# SparkFun_GPS_RTK_Surveyor.net
KiCad netlist of a schematic drawn in EAGLE
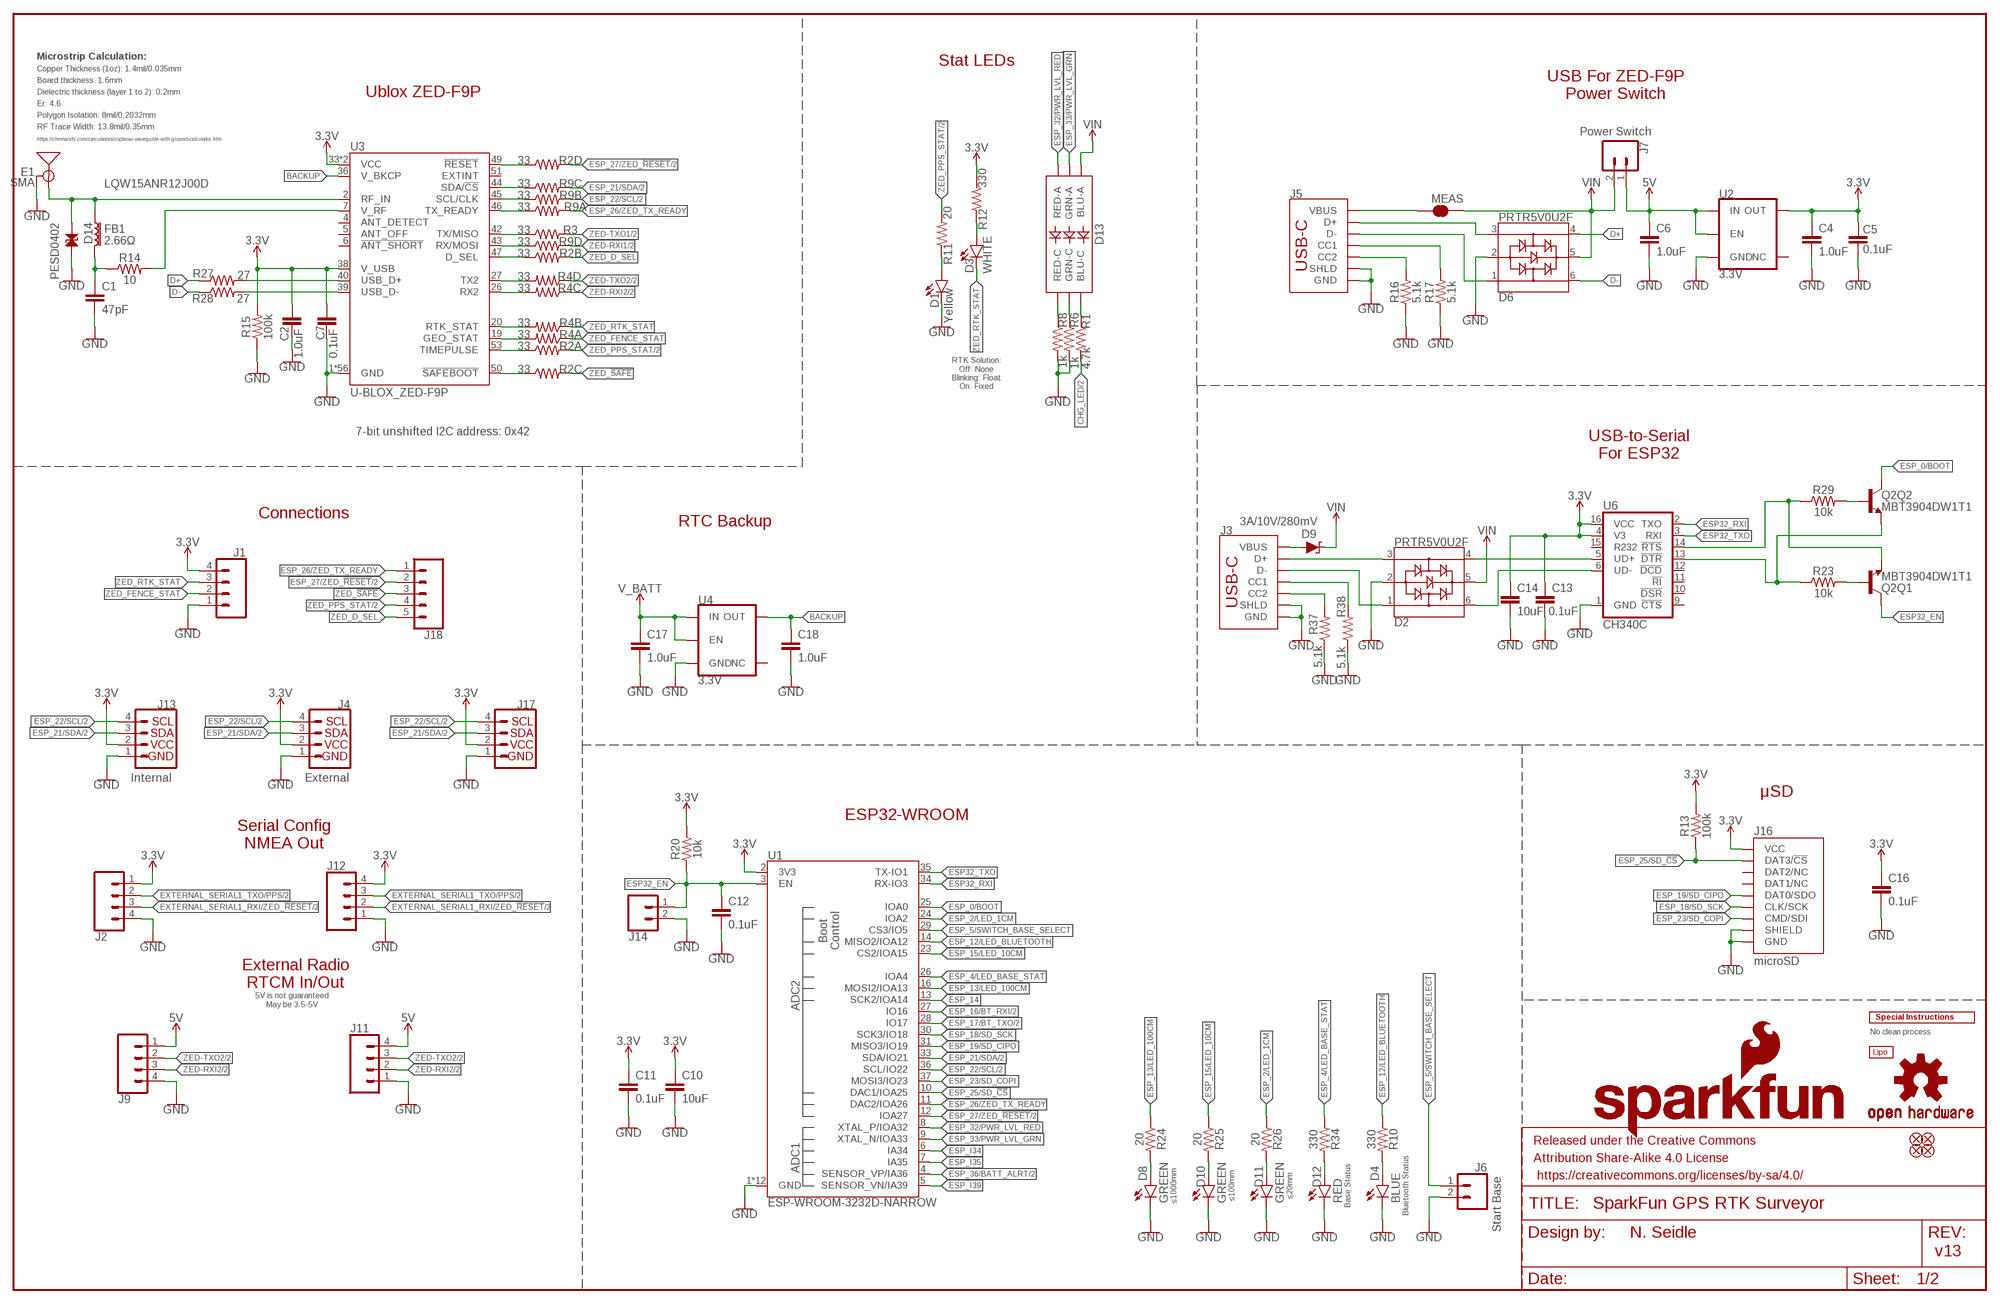
[diagram p0: schematic, sheet 1]
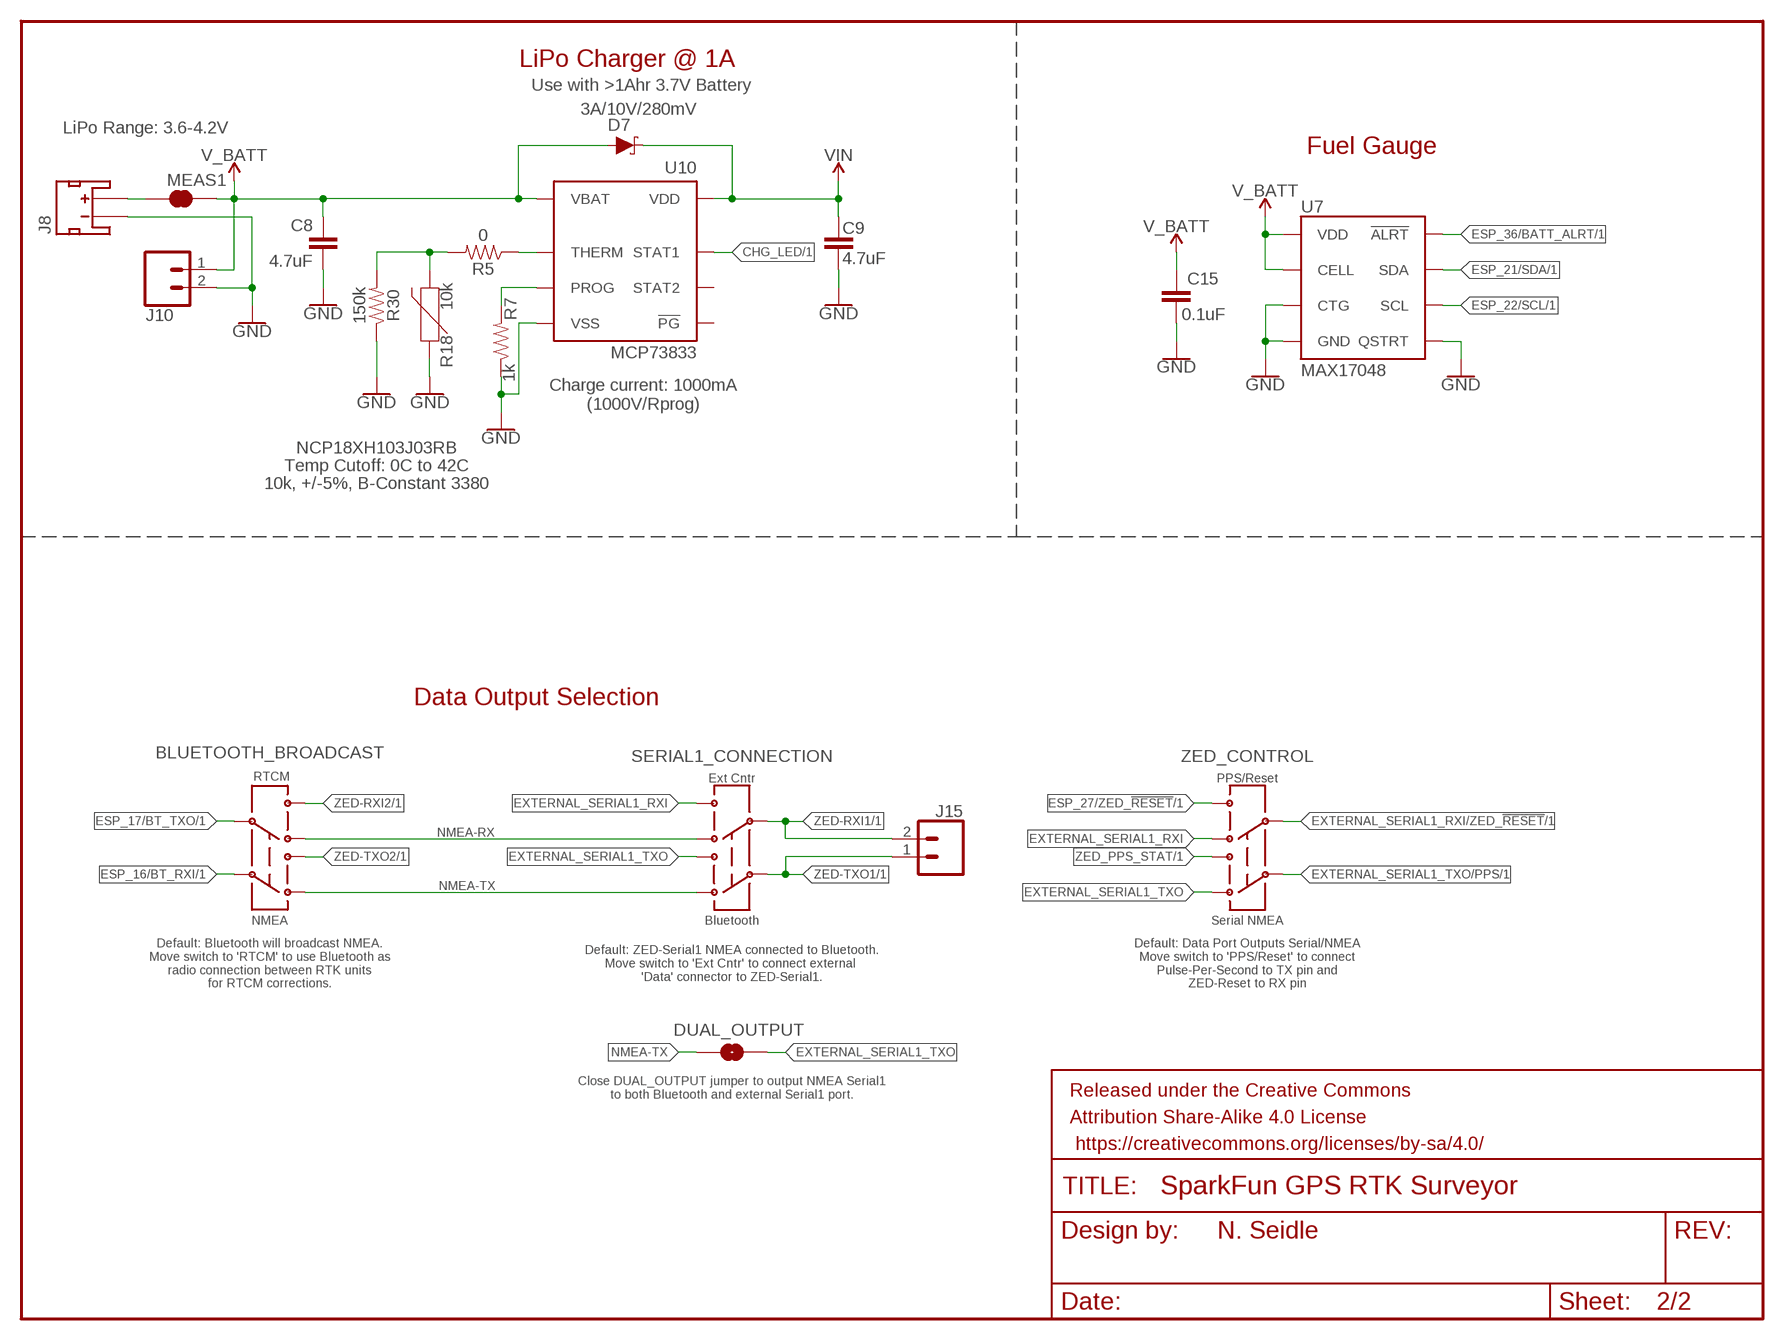
[diagram p1: schematic, sheet 2]

(export (version "E")
  (design (tool "Eeschema 10.0.6"))
  (components
    (comp (ref "BT1")
      (value "LIPO-OUTLINE1000")
      (footprint "eagle-import:LIPO-1000")
      (libsource (lib "eagle-import") (part "LIPO-OUTLINE1000"))
    )
    (comp (ref "C1")
      (value "47pF")
      (footprint "eagle-import:0402")
      (libsource (lib "eagle-import") (part "47PF-0402-25V-5%-X7R"))
    )
    (comp (ref "C2")
      (value "1.0uF")
      (footprint "eagle-import:0603")
      (libsource (lib "eagle-import") (part "1.0UF-0603-16V-10%-X7R"))
    )
    (comp (ref "C4")
      (value "1.0uF")
      (footprint "eagle-import:0603")
      (libsource (lib "eagle-import") (part "1.0UF-0603-16V-10%-X7R"))
    )
    (comp (ref "C5")
      (value "0.1uF")
      (footprint "eagle-import:0603")
      (libsource (lib "eagle-import") (part "0.1UF-0603-25V-5%"))
    )
    (comp (ref "C6")
      (value "1.0uF")
      (footprint "eagle-import:0603")
      (libsource (lib "eagle-import") (part "1.0UF-0603-16V-10%-X7R"))
    )
    (comp (ref "C7")
      (value "0.1uF")
      (footprint "eagle-import:0603")
      (libsource (lib "eagle-import") (part "0.1UF-0603-25V-5%"))
    )
    (comp (ref "C10")
      (value "10uF")
      (footprint "eagle-import:0603")
      (libsource (lib "eagle-import") (part "10UF-0603-6.3V-20%"))
    )
    (comp (ref "C11")
      (value "0.1uF")
      (footprint "eagle-import:0603")
      (libsource (lib "eagle-import") (part "0.1UF-0603-25V-(+80/-20%)"))
    )
    (comp (ref "C12")
      (value "0.1uF")
      (footprint "eagle-import:0603")
      (libsource (lib "eagle-import") (part "0.1UF-0603-25V-(+80/-20%)"))
    )
    (comp (ref "C13")
      (value "0.1uF")
      (footprint "eagle-import:0603")
      (libsource (lib "eagle-import") (part "0.1UF-0603-25V-(+80/-20%)"))
    )
    (comp (ref "C14")
      (value "10uF")
      (footprint "eagle-import:0603")
      (libsource (lib "eagle-import") (part "10UF-0603-6.3V-20%"))
    )
    (comp (ref "C16")
      (value "0.1uF")
      (footprint "eagle-import:0603")
      (libsource (lib "eagle-import") (part "0.1UF-0603-25V-(+80/-20%)"))
    )
    (comp (ref "C17")
      (value "1.0uF")
      (footprint "eagle-import:0603")
      (libsource (lib "eagle-import") (part "1.0UF-0603-16V-10%-X7R"))
    )
    (comp (ref "C18")
      (value "1.0uF")
      (footprint "eagle-import:0603")
      (libsource (lib "eagle-import") (part "1.0UF-0603-16V-10%-X7R"))
    )
    (comp (ref "D1")
      (value "Yellow")
      (footprint "eagle-import:LED-0603")
      (libsource (lib "eagle-import") (part "LED-YELLOW0603"))
    )
    (comp (ref "D2")
      (value "PRTR5V0U2F")
      (footprint "eagle-import:SOT886")
      (libsource (lib "eagle-import") (part "PRTR5V0U2F"))
    )
    (comp (ref "D3")
      (value "WHITE")
      (footprint "eagle-import:LED-0603")
      (libsource (lib "eagle-import") (part "LED-WHITE0603"))
    )
    (comp (ref "D4")
      (value "BLUE")
      (footprint "eagle-import:LED-0603")
      (libsource (lib "eagle-import") (part "LED-BLUE0603"))
    )
    (comp (ref "D6")
      (value "PRTR5V0U2F")
      (footprint "eagle-import:SOT886")
      (libsource (lib "eagle-import") (part "PRTR5V0U2F"))
    )
    (comp (ref "D8")
      (value "GREEN")
      (footprint "eagle-import:LED-0603")
      (libsource (lib "eagle-import") (part "LED-GREEN0603"))
    )
    (comp (ref "D9")
      (value "3A/10V/280mV")
      (footprint "eagle-import:SOD-323")
      (libsource (lib "eagle-import") (part "DIODE-SCHOTTKY-BAT60A"))
    )
    (comp (ref "D10")
      (value "GREEN")
      (footprint "eagle-import:LED-0603")
      (libsource (lib "eagle-import") (part "LED-GREEN0603"))
    )
    (comp (ref "D11")
      (value "GREEN")
      (footprint "eagle-import:LED-0603")
      (libsource (lib "eagle-import") (part "LED-GREEN0603"))
    )
    (comp (ref "D12")
      (value "RED")
      (footprint "eagle-import:LED-0603")
      (libsource (lib "eagle-import") (part "LED-RED0603"))
    )
    (comp (ref "D13")
      (value "LED-RGBBRG")
      (footprint "eagle-import:LED-TRICOLOR-5050")
      (libsource (lib "eagle-import") (part "LED-RGBBRG"))
    )
    (comp (ref "D14")
      (value "PESD0402")
      (footprint "eagle-import:0402")
      (fields
        (field (name "DIGIKEY_PART") "PESD0402-140CT-ND")
        (field (name "MOUSE_PART") "650-PESD0402-140")
      )
      (libsource (lib "eagle-import") (part "PESD0402"))
    )
    (comp (ref "E1")
      (value "SMA")
      (footprint "eagle-import:SMA-EDGE")
      (libsource (lib "eagle-import") (part "ANTENNA-SMA-GROUNDEDEDGE_SMA"))
    )
    (comp (ref "FB1")
      (value "2.66Ω")
      (footprint "eagle-import:0402-TIGHT")
      (libsource (lib "eagle-import") (part "FERRITE_BEAD-0402-2.66Ω-1GHZ"))
    )
    (comp (ref "FRAME2")
      (value "FRAME-LEDGER")
      (footprint "eagle-import:CREATIVE_COMMONS")
      (libsource (lib "eagle-import") (part "FRAME-LEDGER"))
    )
    (comp (ref "J1")
      (value "CONN_041X04_NO_SILK_NO_POP")
      (footprint "eagle-import:1X04_NO_SILK")
      (libsource (lib "eagle-import") (part "CONN_041X04_NO_SILK_NO_POP"))
    )
    (comp (ref "J2")
      (value "CONN_04JST-SMD-LOCKING")
      (footprint "eagle-import:JST-4-SMD-1.25MM-LOCKING")
      (libsource (lib "eagle-import") (part "CONN_04JST-SMD-LOCKING"))
    )
    (comp (ref "J3")
      (value "USB Female Type C Connector")
      (footprint "eagle-import:USB-C-16P_4LAYER-PADS")
      (libsource (lib "eagle-import") (part "USB_C_4-LAYER_PADS"))
    )
    (comp (ref "J4")
      (value "External")
      (footprint "eagle-import:JST04_1MM_RA")
      (libsource (lib "eagle-import") (part "I2C_STANDARDQWIIC"))
    )
    (comp (ref "J5")
      (value "USB Female Type C Connector")
      (footprint "eagle-import:USB-C-16P_4LAYER-PADS")
      (libsource (lib "eagle-import") (part "USB_C_4-LAYER_PADS"))
    )
    (comp (ref "J6")
      (value "Start Base")
      (footprint "eagle-import:JST-2-SMD")
      (libsource (lib "eagle-import") (part "CONN_02-JST-2MM-SMT"))
    )
    (comp (ref "J7")
      (value "Power Switch")
      (footprint "eagle-import:JST-2-SMD")
      (libsource (lib "eagle-import") (part "CONN_02-JST-2MM-SMT"))
    )
    (comp (ref "J9")
      (value "CONN_04JST-SMD-LOCKING")
      (footprint "eagle-import:JST-4-SMD-1.25MM-LOCKING")
      (libsource (lib "eagle-import") (part "CONN_04JST-SMD-LOCKING"))
    )
    (comp (ref "J11")
      (value "CONN_041X04_NO_SILK_NO_POP")
      (footprint "eagle-import:1X04_NO_SILK")
      (libsource (lib "eagle-import") (part "CONN_041X04_NO_SILK_NO_POP"))
    )
    (comp (ref "J12")
      (value "CONN_041X04_NO_SILK_NO_POP")
      (footprint "eagle-import:1X04_NO_SILK")
      (libsource (lib "eagle-import") (part "CONN_041X04_NO_SILK_NO_POP"))
    )
    (comp (ref "J13")
      (value "Internal")
      (footprint "eagle-import:JST04_1MM_RA")
      (libsource (lib "eagle-import") (part "I2C_STANDARDQWIIC"))
    )
    (comp (ref "J14")
      (value "CONN_021X02_NO_SILK")
      (footprint "eagle-import:1X02_NO_SILK")
      (libsource (lib "eagle-import") (part "CONN_021X02_NO_SILK"))
    )
    (comp (ref "J16")
      (value "microSD")
      (footprint "eagle-import:MICRO-SD-SOCKET")
      (libsource (lib "eagle-import") (part "MICRO-SD-SDIOPUSH-PUSH"))
    )
    (comp (ref "J17")
      (value "Qwiic Right Angle")
      (footprint "eagle-import:1X04_NO_SILK")
      (libsource (lib "eagle-import") (part "I2C_STANDARD_NO_SILK"))
    )
    (comp (ref "J18")
      (value "CONN_05NO_SILK")
      (footprint "eagle-import:1X05_NO_SILK")
      (libsource (lib "eagle-import") (part "CONN_05NO_SILK"))
    )
    (comp (ref "JP21")
      (value "FIDUCIALUFIDUCIAL")
      (footprint "eagle-import:FIDUCIAL-MICRO")
      (libsource (lib "eagle-import") (part "FIDUCIALUFIDUCIAL"))
    )
    (comp (ref "JP61")
      (value "FIDUCIALUFIDUCIAL")
      (footprint "eagle-import:FIDUCIAL-MICRO")
      (libsource (lib "eagle-import") (part "FIDUCIALUFIDUCIAL"))
    )
    (comp (ref "JP71")
      (value "FIDUCIALUFIDUCIAL")
      (footprint "eagle-import:FIDUCIAL-MICRO")
      (libsource (lib "eagle-import") (part "FIDUCIALUFIDUCIAL"))
    )
    (comp (ref "JP81")
      (value "FIDUCIALUFIDUCIAL")
      (footprint "eagle-import:FIDUCIAL-MICRO")
      (libsource (lib "eagle-import") (part "FIDUCIALUFIDUCIAL"))
    )
    (comp (ref "LOGO1")
      (value "OSHW-LOGOMINI")
      (footprint "eagle-import:OSHW-LOGO-MINI")
      (libsource (lib "eagle-import") (part "OSHW-LOGOMINI"))
    )
    (comp (ref "LOGO2")
      (value "SFE_LOGO_NAME_FLAME.1_INCH")
      (footprint "eagle-import:SFE_LOGO_NAME_FLAME_.1")
      (libsource (lib "eagle-import") (part "SFE_LOGO_NAME_FLAME.1_INCH"))
    )
    (comp (ref "MEAS")
      (value "JUMPER-COMBO_2_NC_TRACE")
      (footprint "eagle-import:COMBO-JUMPER_2_NC_TRACE")
      (libsource (lib "eagle-import") (part "JUMPER-COMBO_2_NC_TRACE"))
    )
    (comp (ref "Q2")
      (value "MBT3904DW1T1")
      (footprint "eagle-import:SC70-6")
      (libsource (lib "eagle-import") (part "TRANS_NPN_DUAL-MBT3904DW1T1"))
    )
    (comp (ref "R1")
      (value "4.7k")
      (footprint "eagle-import:0603")
      (libsource (lib "eagle-import") (part "4.7KOHM-0603-1/10W-1%"))
    )
    (comp (ref "R2")
      (value "33")
      (footprint "eagle-import:1206_RA")
      (libsource (lib "eagle-import") (part "33OHM_RA-1206-1/16W-5%"))
    )
    (comp (ref "R3")
      (value "33")
      (footprint "eagle-import:0603")
      (libsource (lib "eagle-import") (part "33OHM-0603-1/10W-1%"))
    )
    (comp (ref "R4")
      (value "33")
      (footprint "eagle-import:1206_RA")
      (libsource (lib "eagle-import") (part "33OHM_RA-1206-1/16W-5%"))
    )
    (comp (ref "R6")
      (value "1k")
      (footprint "eagle-import:0603")
      (libsource (lib "eagle-import") (part "1KOHM-0603-1/10W-1%"))
    )
    (comp (ref "R8")
      (value "1k")
      (footprint "eagle-import:0603")
      (libsource (lib "eagle-import") (part "1KOHM-0603-1/10W-1%"))
    )
    (comp (ref "R9")
      (value "33")
      (footprint "eagle-import:1206_RA")
      (libsource (lib "eagle-import") (part "33OHM_RA-1206-1/16W-5%"))
    )
    (comp (ref "R10")
      (value "330")
      (footprint "eagle-import:0603")
      (libsource (lib "eagle-import") (part "330OHM-0603-1/10W-1%"))
    )
    (comp (ref "R11")
      (value "20")
      (footprint "eagle-import:0603")
      (libsource (lib "eagle-import") (part "20OHM-0603-1/10W-1%"))
    )
    (comp (ref "R12")
      (value "330")
      (footprint "eagle-import:0603")
      (libsource (lib "eagle-import") (part "330OHM-0603-1/10W-1%"))
    )
    (comp (ref "R13")
      (value "100k")
      (footprint "eagle-import:0603")
      (libsource (lib "eagle-import") (part "100KOHM-0603-1/10W-1%"))
    )
    (comp (ref "R14")
      (value "10")
      (footprint "eagle-import:0603")
      (libsource (lib "eagle-import") (part "10OHM-0603-1/10W-1%"))
    )
    (comp (ref "R15")
      (value "100k")
      (footprint "eagle-import:0603")
      (libsource (lib "eagle-import") (part "100KOHM-0603-1/10W-1%"))
    )
    (comp (ref "R16")
      (value "5.1k")
      (footprint "eagle-import:0603")
      (libsource (lib "eagle-import") (part "5.1KOHM5.1KOHM-0603-1/10W-1%"))
    )
    (comp (ref "R17")
      (value "5.1k")
      (footprint "eagle-import:0603")
      (libsource (lib "eagle-import") (part "5.1KOHM5.1KOHM-0603-1/10W-1%"))
    )
    (comp (ref "R20")
      (value "10k")
      (footprint "eagle-import:0603")
      (libsource (lib "eagle-import") (part "10KOHM-0603-1/10W-1%"))
    )
    (comp (ref "R23")
      (value "10k")
      (footprint "eagle-import:0603")
      (libsource (lib "eagle-import") (part "10KOHM-0603-1/10W-1%"))
    )
    (comp (ref "R24")
      (value "20")
      (footprint "eagle-import:0603")
      (libsource (lib "eagle-import") (part "20OHM-0603-1/10W-1%"))
    )
    (comp (ref "R25")
      (value "20")
      (footprint "eagle-import:0603")
      (libsource (lib "eagle-import") (part "20OHM-0603-1/10W-1%"))
    )
    (comp (ref "R26")
      (value "20")
      (footprint "eagle-import:0603")
      (libsource (lib "eagle-import") (part "20OHM-0603-1/10W-1%"))
    )
    (comp (ref "R27")
      (value "27")
      (footprint "eagle-import:0603")
      (libsource (lib "eagle-import") (part "27OHM-0603-1/10W-1%"))
    )
    (comp (ref "R28")
      (value "27")
      (footprint "eagle-import:0603")
      (libsource (lib "eagle-import") (part "27OHM-0603-1/10W-1%"))
    )
    (comp (ref "R29")
      (value "10k")
      (footprint "eagle-import:0603")
      (libsource (lib "eagle-import") (part "10KOHM-0603-1/10W-1%"))
    )
    (comp (ref "R34")
      (value "330")
      (footprint "eagle-import:0603")
      (libsource (lib "eagle-import") (part "330OHM-0603-1/10W-1%"))
    )
    (comp (ref "R37")
      (value "5.1k")
      (footprint "eagle-import:0603")
      (libsource (lib "eagle-import") (part "5.1KOHM5.1KOHM-0603-1/10W-1%"))
    )
    (comp (ref "R38")
      (value "5.1k")
      (footprint "eagle-import:0603")
      (libsource (lib "eagle-import") (part "5.1KOHM5.1KOHM-0603-1/10W-1%"))
    )
    (comp (ref "U$2")
      (value "SPECIAL_INSTRUCTIONS-ORDERING")
      (footprint "eagle-import:ORDERING_INSTRUCTIONS")
      (libsource (lib "eagle-import") (part "SPECIAL_INSTRUCTIONS-ORDERING"))
    )
    (comp (ref "U1")
      (value "ESP-WROOM-3232D-NARROW")
      (footprint "eagle-import:ESP-WROOM-32D-NARROW")
      (libsource (lib "eagle-import") (part "ESP-WROOM-3232D-NARROW"))
    )
    (comp (ref "U2")
      (value "3.3V")
      (footprint "eagle-import:SOT23-5")
      (libsource (lib "eagle-import") (part "V_REG_AP2112K-3.3V"))
    )
    (comp (ref "U3")
      (value "U-BLOX_ZED-F9P")
      (footprint "eagle-import:ZED-F9P")
      (libsource (lib "eagle-import") (part "U-BLOX_ZED-F9P"))
    )
    (comp (ref "U4")
      (value "3.3V")
      (footprint "eagle-import:SOT23-5")
      (libsource (lib "eagle-import") (part "V_REG_AP2112K-3.3V"))
    )
    (comp (ref "U6")
      (value "CH340C")
      (footprint "eagle-import:SO016")
      (libsource (lib "eagle-import") (part "CH340C"))
    )
    (comp (ref "BLUETOOTH_BROADCAST")
      (value "SWITCH-DPDT-SMD-AYZ0202")
      (footprint "eagle-import:SWITCH_DPDT_SMD_AYZ0202")
      (libsource (lib "eagle-import") (part "SWITCH-DPDT-SMD-AYZ0202"))
    )
    (comp (ref "C8")
      (value "4.7uF")
      (footprint "eagle-import:0603")
      (libsource (lib "eagle-import") (part "4.7UF-0603-35V-(20%)"))
    )
    (comp (ref "C9")
      (value "4.7uF")
      (footprint "eagle-import:0603")
      (libsource (lib "eagle-import") (part "4.7UF-0603-35V-(20%)"))
    )
    (comp (ref "C15")
      (value "0.1uF")
      (footprint "eagle-import:0603")
      (libsource (lib "eagle-import") (part "0.1UF-0603-25V-(+80/-20%)"))
    )
    (comp (ref "D7")
      (value "3A/10V/280mV")
      (footprint "eagle-import:SOD-323")
      (libsource (lib "eagle-import") (part "DIODE-SCHOTTKY-BAT60A"))
    )
    (comp (ref "DUAL_OUTPUT")
      (value "JUMPER-SMT_2_NO_SILK")
      (footprint "eagle-import:SMT-JUMPER_2_NO_SILK")
      (libsource (lib "eagle-import") (part "JUMPER-SMT_2_NO_SILK"))
    )
    (comp (ref "FRAME1")
      (value "FRAME-LETTERNO_PACKAGE")
      (footprint "eagle-import:DUMMY")
      (fields (field (name "DESIGNER") "Nobody"))
      (libsource (lib "eagle-import") (part "FRAME-LETTERNO_PACKAGE"))
    )
    (comp (ref "J8")
      (value "JST_2MM_MALE")
      (footprint "eagle-import:JST-2-SMD")
      (libsource (lib "eagle-import") (part "JST_2MM_MALE"))
    )
    (comp (ref "J10")
      (value "CONN_021X02_NO_SILK")
      (footprint "eagle-import:1X02_NO_SILK")
      (libsource (lib "eagle-import") (part "CONN_021X02_NO_SILK"))
    )
    (comp (ref "J15")
      (value "CONN_021X02_NO_SILK")
      (footprint "eagle-import:1X02_NO_SILK")
      (libsource (lib "eagle-import") (part "CONN_021X02_NO_SILK"))
    )
    (comp (ref "MEAS1")
      (value "JUMPER-COMBO_2_NC_TRACE")
      (footprint "eagle-import:COMBO-JUMPER_2_NC_TRACE")
      (libsource (lib "eagle-import") (part "JUMPER-COMBO_2_NC_TRACE"))
    )
    (comp (ref "R5")
      (value "0")
      (footprint "eagle-import:0603")
      (libsource (lib "eagle-import") (part "0OHM-0603-1/10W"))
    )
    (comp (ref "R7")
      (value "1k")
      (footprint "eagle-import:0603")
      (libsource (lib "eagle-import") (part "1KOHM-0603-1/10W-1%"))
    )
    (comp (ref "R18")
      (value "10k")
      (footprint "eagle-import:0603")
      (libsource (lib "eagle-import") (part "NTC-THERMISTOR-0603"))
    )
    (comp (ref "R30")
      (value "150k")
      (footprint "eagle-import:0603")
      (libsource (lib "eagle-import") (part "150KOHM-0603-1/10W-1%"))
    )
    (comp (ref "SERIAL1_CONNECTION")
      (value "SWITCH-DPDT-SMD-AYZ0202")
      (footprint "eagle-import:SWITCH_DPDT_SMD_AYZ0202")
      (libsource (lib "eagle-import") (part "SWITCH-DPDT-SMD-AYZ0202"))
    )
    (comp (ref "U7")
      (value "MAX17048")
      (footprint "eagle-import:DFN-8")
      (libsource (lib "eagle-import") (part "MAX17048DFN8"))
    )
    (comp (ref "U10")
      (value "MCP73833")
      (footprint "eagle-import:DFN-10")
      (libsource (lib "eagle-import") (part "MCP73833"))
    )
    (comp (ref "ZED_CONTROL")
      (value "SWITCH-DPDT-SMD-AYZ0202")
      (footprint "eagle-import:SWITCH_DPDT_SMD_AYZ0202")
      (libsource (lib "eagle-import") (part "SWITCH-DPDT-SMD-AYZ0202"))
    )
  )
  (nets
    (net (code "1") (name "3.3V") (class "Default")
      (node (ref "C10") (pin "1") (pinfunction "1_1") (pintype "passive"))
      (node (ref "C11") (pin "1") (pinfunction "1_1") (pintype "passive"))
      (node (ref "C13") (pin "1") (pinfunction "1_1") (pintype "passive"))
      (node (ref "C14") (pin "1") (pinfunction "1_1") (pintype "passive"))
      (node (ref "C16") (pin "1") (pinfunction "1_1") (pintype "passive"))
      (node (ref "C2") (pin "1") (pinfunction "1_1") (pintype "passive"))
      (node (ref "C4") (pin "1") (pinfunction "1_1") (pintype "passive"))
      (node (ref "C5") (pin "2") (pinfunction "2_2") (pintype "passive"))
      (node (ref "C7") (pin "2") (pinfunction "2_2") (pintype "passive"))
      (node (ref "J1") (pin "4") (pinfunction "4_4") (pintype "passive"))
      (node (ref "J12") (pin "4") (pinfunction "4_4") (pintype "passive"))
      (node (ref "J13") (pin "2") (pinfunction "2_2") (pintype "power_in"))
      (node (ref "J16") (pin "VCC") (pinfunction "VCC_VCC") (pintype "bidirectional"))
      (node (ref "J17") (pin "2") (pinfunction "2_2") (pintype "power_in"))
      (node (ref "J2") (pin "1") (pinfunction "1_1") (pintype "passive"))
      (node (ref "J4") (pin "2") (pinfunction "2_2") (pintype "power_in"))
      (node (ref "R12") (pin "2") (pinfunction "2_2") (pintype "passive"))
      (node (ref "R13") (pin "2") (pinfunction "2_2") (pintype "passive"))
      (node (ref "R15") (pin "2") (pinfunction "2_2") (pintype "passive"))
      (node (ref "R20") (pin "2") (pinfunction "2_2") (pintype "passive"))
      (node (ref "U1") (pin "2") (pinfunction "3V3_2") (pintype "bidirectional"))
      (node (ref "U2") (pin "5") (pinfunction "OUT_5") (pintype "passive"))
      (node (ref "U3") (pin "33") (pinfunction "VCC_33") (pintype "bidirectional"))
      (node (ref "U3") (pin "34") (pinfunction "VCC_34") (pintype "bidirectional"))
      (node (ref "U3") (pin "38") (pinfunction "V_USB_38") (pintype "bidirectional"))
      (node (ref "U6") (pin "16") (pinfunction "VCC_16") (pintype "bidirectional"))
      (node (ref "U6") (pin "4") (pinfunction "V3_4") (pintype "bidirectional"))
    )
    (net (code "2") (name "5V") (class "Default")
      (node (ref "C6") (pin "1") (pinfunction "1_1") (pintype "passive"))
      (node (ref "J11") (pin "4") (pinfunction "4_4") (pintype "passive"))
      (node (ref "J7") (pin "1") (pinfunction "2_1") (pintype "passive"))
      (node (ref "J9") (pin "1") (pinfunction "1_1") (pintype "passive"))
      (node (ref "U2") (pin "1") (pinfunction "IN_1") (pintype "input"))
      (node (ref "U2") (pin "3") (pinfunction "EN_3") (pintype "input"))
    )
    (net (code "3") (name "BACKUP") (class "Default")
      (node (ref "C18") (pin "1") (pinfunction "1_1") (pintype "passive"))
      (node (ref "U3") (pin "36") (pinfunction "V_BKCP_36") (pintype "bidirectional"))
      (node (ref "U4") (pin "5") (pinfunction "OUT_5") (pintype "passive"))
    )
    (net (code "4") (name "CHG_LED") (class "Default")
      (node (ref "R1") (pin "2") (pinfunction "2_2") (pintype "passive"))
      (node (ref "U10") (pin "3") (pinfunction "STAT1_3") (pintype "bidirectional"))
    )
    (net (code "5") (name "D+") (class "Default")
      (node (ref "D6") (pin "4") (pinfunction "4_4") (pintype "bidirectional"))
      (node (ref "R27") (pin "1") (pinfunction "1_1") (pintype "passive"))
    )
    (net (code "6") (name "D-") (class "Default")
      (node (ref "D6") (pin "6") (pinfunction "6_6") (pintype "bidirectional"))
      (node (ref "R28") (pin "1") (pinfunction "1_1") (pintype "passive"))
    )
    (net (code "7") (name "ESP32_EN") (class "Default")
      (node (ref "C12") (pin "1") (pinfunction "1_1") (pintype "passive"))
      (node (ref "J14") (pin "1") (pinfunction "1_1") (pintype "passive"))
      (node (ref "Q2") (pin "3") (pinfunction "C_3") (pintype "passive"))
      (node (ref "R20") (pin "1") (pinfunction "1_1") (pintype "passive"))
      (node (ref "U1") (pin "3") (pinfunction "EN_3") (pintype "bidirectional"))
    )
    (net (code "8") (name "ESP32_RXI") (class "Default")
      (node (ref "U1") (pin "34") (pinfunction "RX-IO3_34") (pintype "bidirectional"))
      (node (ref "U6") (pin "2") (pinfunction "TXO_2") (pintype "bidirectional"))
    )
    (net (code "9") (name "ESP32_TXO") (class "Default")
      (node (ref "U1") (pin "35") (pinfunction "TX-IO1_35") (pintype "bidirectional"))
      (node (ref "U6") (pin "3") (pinfunction "RXI_3") (pintype "bidirectional"))
    )
    (net (code "10") (name "ESP_0{slash}BOOT") (class "Default")
      (node (ref "Q2") (pin "6") (pinfunction "C_6") (pintype "passive"))
      (node (ref "U1") (pin "25") (pinfunction "IOA0_25") (pintype "bidirectional"))
    )
    (net (code "11") (name "ESP_2{slash}LED_1CM") (class "Default")
      (node (ref "R26") (pin "1") (pinfunction "1_1") (pintype "passive"))
      (node (ref "U1") (pin "24") (pinfunction "IOA2_24") (pintype "bidirectional"))
    )
    (net (code "12") (name "ESP_4{slash}LED_BASE_STAT") (class "Default")
      (node (ref "R34") (pin "1") (pinfunction "1_1") (pintype "passive"))
      (node (ref "U1") (pin "26") (pinfunction "IOA4_26") (pintype "bidirectional"))
    )
    (net (code "13") (name "ESP_5{slash}SWITCH_BASE_SELECT") (class "Default")
      (node (ref "J6") (pin "1") (pinfunction "2_1") (pintype "passive"))
      (node (ref "U1") (pin "29") (pinfunction "CS3/IO5_29") (pintype "bidirectional"))
    )
    (net (code "14") (name "ESP_12{slash}LED_BLUETOOTH") (class "Default")
      (node (ref "R10") (pin "1") (pinfunction "1_1") (pintype "passive"))
      (node (ref "U1") (pin "14") (pinfunction "MISO2/IOA12_14") (pintype "bidirectional"))
    )
    (net (code "15") (name "ESP_13{slash}LED_100CM") (class "Default")
      (node (ref "R24") (pin "1") (pinfunction "1_1") (pintype "passive"))
      (node (ref "U1") (pin "16") (pinfunction "MOSI2/IOA13_16") (pintype "bidirectional"))
    )
    (net (code "16") (name "ESP_14") (class "Default")
      (node (ref "U1") (pin "13") (pinfunction "SCK2/IOA14_13") (pintype "bidirectional"))
    )
    (net (code "17") (name "ESP_15{slash}LED_10CM") (class "Default")
      (node (ref "R25") (pin "1") (pinfunction "1_1") (pintype "passive"))
      (node (ref "U1") (pin "23") (pinfunction "CS2/IOA15_23") (pintype "bidirectional"))
    )
    (net (code "18") (name "ESP_16{slash}BT_RXI") (class "Default")
      (node (ref "BLUETOOTH_BROADCAST") (pin "2") (pinfunction "2_2") (pintype "bidirectional"))
      (node (ref "U1") (pin "27") (pinfunction "IO16_27") (pintype "bidirectional"))
    )
    (net (code "19") (name "ESP_17{slash}BT_TXO") (class "Default")
      (node (ref "BLUETOOTH_BROADCAST") (pin "5") (pinfunction "5_5") (pintype "bidirectional"))
      (node (ref "U1") (pin "28") (pinfunction "IO17_28") (pintype "bidirectional"))
    )
    (net (code "20") (name "ESP_18{slash}SD_SCK") (class "Default")
      (node (ref "J16") (pin "SCLK") (pinfunction "CLK/SCK_SCLK") (pintype "bidirectional"))
      (node (ref "U1") (pin "30") (pinfunction "SCK3/IO18_30") (pintype "bidirectional"))
    )
    (net (code "21") (name "ESP_19{slash}SD_CIPO") (class "Default")
      (node (ref "J16") (pin "DO/DAT0") (pinfunction "DAT0/SDO_DO/DAT0") (pintype "bidirectional"))
      (node (ref "U1") (pin "31") (pinfunction "MISO3/IO19_31") (pintype "bidirectional"))
    )
    (net (code "22") (name "ESP_21{slash}SDA") (class "Default")
      (node (ref "J13") (pin "3") (pinfunction "3_3") (pintype "passive"))
      (node (ref "J17") (pin "3") (pinfunction "3_3") (pintype "passive"))
      (node (ref "J4") (pin "3") (pinfunction "3_3") (pintype "passive"))
      (node (ref "R9") (pin "P6") (pinfunction "2_P6") (pintype "passive"))
      (node (ref "U1") (pin "33") (pinfunction "SDA/IO21_33") (pintype "bidirectional"))
      (node (ref "U7") (pin "8") (pinfunction "SDA_8") (pintype "input"))
    )
    (net (code "23") (name "ESP_22{slash}SCL") (class "Default")
      (node (ref "J13") (pin "4") (pinfunction "4_4") (pintype "passive"))
      (node (ref "J17") (pin "4") (pinfunction "4_4") (pintype "passive"))
      (node (ref "J4") (pin "4") (pinfunction "4_4") (pintype "passive"))
      (node (ref "R9") (pin "P7") (pinfunction "2_P7") (pintype "passive"))
      (node (ref "U1") (pin "36") (pinfunction "SCL/IO22_36") (pintype "bidirectional"))
      (node (ref "U7") (pin "7") (pinfunction "SCL_7") (pintype "output"))
    )
    (net (code "24") (name "ESP_23{slash}SD_COPI") (class "Default")
      (node (ref "J16") (pin "DI/CMD") (pinfunction "CMD/SDI_DI/CMD") (pintype "bidirectional"))
      (node (ref "U1") (pin "37") (pinfunction "MOSI3/IO23_37") (pintype "bidirectional"))
    )
    (net (code "25") (name "ESP_25{slash}SD_~{CS}") (class "Default")
      (node (ref "J16") (pin "CS/DAT3") (pinfunction "DAT3/~{CS}_CS/DAT3") (pintype "bidirectional"))
      (node (ref "R13") (pin "1") (pinfunction "1_1") (pintype "passive"))
      (node (ref "U1") (pin "10") (pinfunction "DAC1/IOA25_10") (pintype "bidirectional"))
    )
    (net (code "26") (name "ESP_26{slash}ZED_TX_READY") (class "Default")
      (node (ref "J18") (pin "1") (pinfunction "1_1") (pintype "passive"))
      (node (ref "R9") (pin "P8") (pinfunction "2_P8") (pintype "passive"))
      (node (ref "U1") (pin "11") (pinfunction "DAC2/IOA26_11") (pintype "bidirectional"))
    )
    (net (code "27") (name "ESP_27{slash}ZED_~{RESET}") (class "Default")
      (node (ref "J18") (pin "2") (pinfunction "2_2") (pintype "passive"))
      (node (ref "R2") (pin "P5") (pinfunction "2_P5") (pintype "passive"))
      (node (ref "U1") (pin "12") (pinfunction "IOA27_12") (pintype "bidirectional"))
      (node (ref "ZED_CONTROL") (pin "4") (pinfunction "4_4") (pintype "bidirectional"))
    )
    (net (code "28") (name "ESP_32{slash}PWR_LVL_RED") (class "Default")
      (node (ref "D13") (pin "5") (pinfunction "RED-A_5") (pintype "bidirectional"))
      (node (ref "U1") (pin "8") (pinfunction "XTAL_P/IOA32_8") (pintype "bidirectional"))
    )
    (net (code "29") (name "ESP_33{slash}PWR_LVL_GRN") (class "Default")
      (node (ref "D13") (pin "4") (pinfunction "GRN-A_4") (pintype "bidirectional"))
      (node (ref "U1") (pin "9") (pinfunction "XTAL_N/IOA33_9") (pintype "bidirectional"))
    )
    (net (code "30") (name "ESP_36{slash}BATT_ALRT") (class "Default")
      (node (ref "U1") (pin "4") (pinfunction "SENSOR_VP/IA36_4") (pintype "bidirectional"))
      (node (ref "U7") (pin "5") (pinfunction "~{ALRT}_5") (pintype "bidirectional"))
    )
    (net (code "31") (name "ESP_I34") (class "Default")
      (node (ref "U1") (pin "6") (pinfunction "IA34_6") (pintype "bidirectional"))
    )
    (net (code "32") (name "ESP_I35") (class "Default")
      (node (ref "U1") (pin "7") (pinfunction "IA35_7") (pintype "bidirectional"))
    )
    (net (code "33") (name "ESP_I39") (class "Default")
      (node (ref "U1") (pin "5") (pinfunction "SENSOR_VN/IA39_5") (pintype "bidirectional"))
    )
    (net (code "34") (name "EXTERNAL_SERIAL1_RXI") (class "Default")
      (node (ref "SERIAL1_CONNECTION") (pin "4") (pinfunction "4_4") (pintype "bidirectional"))
      (node (ref "ZED_CONTROL") (pin "6") (pinfunction "6_6") (pintype "bidirectional"))
    )
    (net (code "35") (name "EXTERNAL_SERIAL1_RXI{slash}ZED_~{RESET}") (class "Default")
      (node (ref "J12") (pin "2") (pinfunction "2_2") (pintype "passive"))
      (node (ref "J2") (pin "3") (pinfunction "3_3") (pintype "passive"))
      (node (ref "ZED_CONTROL") (pin "5") (pinfunction "5_5") (pintype "bidirectional"))
    )
    (net (code "36") (name "EXTERNAL_SERIAL1_TXO") (class "Default")
      (node (ref "DUAL_OUTPUT") (pin "2") (pinfunction "2_2") (pintype "passive"))
      (node (ref "SERIAL1_CONNECTION") (pin "1") (pinfunction "1_1") (pintype "bidirectional"))
      (node (ref "ZED_CONTROL") (pin "3") (pinfunction "3_3") (pintype "bidirectional"))
    )
    (net (code "37") (name "EXTERNAL_SERIAL1_TXO{slash}PPS") (class "Default")
      (node (ref "J12") (pin "3") (pinfunction "3_3") (pintype "passive"))
      (node (ref "J2") (pin "2") (pinfunction "2_2") (pintype "passive"))
      (node (ref "ZED_CONTROL") (pin "2") (pinfunction "2_2") (pintype "bidirectional"))
    )
    (net (code "38") (name "GND") (class "Default")
      (node (ref "C1") (pin "2") (pinfunction "2_2") (pintype "passive"))
      (node (ref "C10") (pin "2") (pinfunction "2_2") (pintype "passive"))
      (node (ref "C11") (pin "2") (pinfunction "2_2") (pintype "passive"))
      (node (ref "C12") (pin "2") (pinfunction "2_2") (pintype "passive"))
      (node (ref "C13") (pin "2") (pinfunction "2_2") (pintype "passive"))
      (node (ref "C14") (pin "2") (pinfunction "2_2") (pintype "passive"))
      (node (ref "C15") (pin "2") (pinfunction "2_2") (pintype "passive"))
      (node (ref "C16") (pin "2") (pinfunction "2_2") (pintype "passive"))
      (node (ref "C17") (pin "2") (pinfunction "2_2") (pintype "passive"))
      (node (ref "C18") (pin "2") (pinfunction "2_2") (pintype "passive"))
      (node (ref "C2") (pin "2") (pinfunction "2_2") (pintype "passive"))
      (node (ref "C4") (pin "2") (pinfunction "2_2") (pintype "passive"))
      (node (ref "C5") (pin "1") (pinfunction "1_1") (pintype "passive"))
      (node (ref "C6") (pin "2") (pinfunction "2_2") (pintype "passive"))
      (node (ref "C7") (pin "1") (pinfunction "1_1") (pintype "passive"))
      (node (ref "C8") (pin "2") (pinfunction "2_2") (pintype "passive"))
      (node (ref "C9") (pin "2") (pinfunction "2_2") (pintype "passive"))
      (node (ref "D1") (pin "C") (pinfunction "C_C") (pintype "passive"))
      (node (ref "D10") (pin "C") (pinfunction "C_C") (pintype "passive"))
      (node (ref "D11") (pin "C") (pinfunction "C_C") (pintype "passive"))
      (node (ref "D12") (pin "C") (pinfunction "C_C") (pintype "passive"))
      (node (ref "D14") (pin "2") (pinfunction "2_2") (pintype "bidirectional"))
      (node (ref "D2") (pin "2") (pinfunction "2_2") (pintype "power_in"))
      (node (ref "D4") (pin "C") (pinfunction "C_C") (pintype "passive"))
      (node (ref "D6") (pin "2") (pinfunction "2_2") (pintype "power_in"))
      (node (ref "D8") (pin "C") (pinfunction "C_C") (pintype "passive"))
      (node (ref "E1") (pin "GND@0") (pinfunction "GND_GND@0") (pintype "bidirectional"))
      (node (ref "E1") (pin "GND@1") (pinfunction "GND_GND@1") (pintype "bidirectional"))
      (node (ref "E1") (pin "GND@2") (pinfunction "GND_GND@2") (pintype "bidirectional"))
      (node (ref "E1") (pin "GND@3") (pinfunction "GND_GND@3") (pintype "bidirectional"))
      (node (ref "J1") (pin "1") (pinfunction "1_1") (pintype "passive"))
      (node (ref "J10") (pin "2") (pinfunction "2_2") (pintype "passive"))
      (node (ref "J11") (pin "1") (pinfunction "1_1") (pintype "passive"))
      (node (ref "J12") (pin "1") (pinfunction "1_1") (pintype "passive"))
      (node (ref "J13") (pin "1") (pinfunction "1_1") (pintype "power_in"))
      (node (ref "J14") (pin "2") (pinfunction "2_2") (pintype "passive"))
      (node (ref "J16") (pin "CD1") (pinfunction "SHIELD_CD1") (pintype "bidirectional"))
      (node (ref "J16") (pin "GND") (pinfunction "GND_GND") (pintype "bidirectional"))
      (node (ref "J16") (pin "GND1") (pinfunction "GND_GND1") (pintype "bidirectional"))
      (node (ref "J16") (pin "GND3") (pinfunction "GND_GND3") (pintype "bidirectional"))
      (node (ref "J17") (pin "1") (pinfunction "1_1") (pintype "power_in"))
      (node (ref "J2") (pin "4") (pinfunction "4_4") (pintype "passive"))
      (node (ref "J3") (pin "GND") (pinfunction "GND_GND") (pintype "bidirectional"))
      (node (ref "J3") (pin "GND2") (pinfunction "GND_GND2") (pintype "bidirectional"))
      (node (ref "J3") (pin "SHLD1") (pinfunction "SHLD_SHLD1") (pintype "bidirectional"))
      (node (ref "J3") (pin "SHLD2") (pinfunction "SHLD_SHLD2") (pintype "bidirectional"))
      (node (ref "J3") (pin "SHLD3") (pinfunction "SHLD_SHLD3") (pintype "bidirectional"))
      (node (ref "J3") (pin "SHLD4") (pinfunction "SHLD_SHLD4") (pintype "bidirectional"))
      (node (ref "J4") (pin "1") (pinfunction "1_1") (pintype "power_in"))
      (node (ref "J5") (pin "GND") (pinfunction "GND_GND") (pintype "bidirectional"))
      (node (ref "J5") (pin "GND2") (pinfunction "GND_GND2") (pintype "bidirectional"))
      (node (ref "J5") (pin "SHLD1") (pinfunction "SHLD_SHLD1") (pintype "bidirectional"))
      (node (ref "J5") (pin "SHLD2") (pinfunction "SHLD_SHLD2") (pintype "bidirectional"))
      (node (ref "J5") (pin "SHLD3") (pinfunction "SHLD_SHLD3") (pintype "bidirectional"))
      (node (ref "J5") (pin "SHLD4") (pinfunction "SHLD_SHLD4") (pintype "bidirectional"))
      (node (ref "J6") (pin "2") (pinfunction "1_2") (pintype "passive"))
      (node (ref "J8") (pin "1") (pinfunction "-_1") (pintype "bidirectional"))
      (node (ref "J9") (pin "4") (pinfunction "4_4") (pintype "passive"))
      (node (ref "R15") (pin "1") (pinfunction "1_1") (pintype "passive"))
      (node (ref "R16") (pin "1") (pinfunction "1_1") (pintype "passive"))
      (node (ref "R17") (pin "1") (pinfunction "1_1") (pintype "passive"))
      (node (ref "R18") (pin "1") (pinfunction "1_1") (pintype "bidirectional"))
      (node (ref "R30") (pin "1") (pinfunction "1_1") (pintype "passive"))
      (node (ref "R37") (pin "1") (pinfunction "1_1") (pintype "passive"))
      (node (ref "R38") (pin "1") (pinfunction "1_1") (pintype "passive"))
      (node (ref "R6") (pin "2") (pinfunction "2_2") (pintype "passive"))
      (node (ref "R7") (pin "1") (pinfunction "1_1") (pintype "passive"))
      (node (ref "R8") (pin "2") (pinfunction "2_2") (pintype "passive"))
      (node (ref "U1") (pin "1") (pinfunction "GND_1") (pintype "bidirectional"))
      (node (ref "U1") (pin "15") (pinfunction "GND_15") (pintype "bidirectional"))
      (node (ref "U1") (pin "38") (pinfunction "GND_38") (pintype "bidirectional"))
      (node (ref "U1") (pin "GND1") (pinfunction "GND_GND1") (pintype "bidirectional"))
      (node (ref "U1") (pin "GNDT1") (pinfunction "GND_GNDT1") (pintype "bidirectional"))
      (node (ref "U1") (pin "GNDT2") (pinfunction "GND_GNDT2") (pintype "bidirectional"))
      (node (ref "U1") (pin "GNDT3") (pinfunction "GND_GNDT3") (pintype "bidirectional"))
      (node (ref "U1") (pin "GNDT4") (pinfunction "GND_GNDT4") (pintype "bidirectional"))
      (node (ref "U1") (pin "GNDT5") (pinfunction "GND_GNDT5") (pintype "bidirectional"))
      (node (ref "U1") (pin "GNDT6") (pinfunction "GND_GNDT6") (pintype "bidirectional"))
      (node (ref "U1") (pin "GNDT7") (pinfunction "GND_GNDT7") (pintype "bidirectional"))
      (node (ref "U1") (pin "GNDT8") (pinfunction "GND_GNDT8") (pintype "bidirectional"))
      (node (ref "U10") (pin "11") (pinfunction "VSS_11") (pintype "bidirectional"))
      (node (ref "U10") (pin "5") (pinfunction "VSS_5") (pintype "bidirectional"))
      (node (ref "U2") (pin "2") (pinfunction "GND_2") (pintype "input"))
      (node (ref "U3") (pin "1") (pinfunction "GND_1") (pintype "bidirectional"))
      (node (ref "U3") (pin "100") (pinfunction "GND_100") (pintype "bidirectional"))
      (node (ref "U3") (pin "101") (pinfunction "GND_101") (pintype "bidirectional"))
      (node (ref "U3") (pin "102") (pinfunction "GND_102") (pintype "bidirectional"))
      (node (ref "U3") (pin "12") (pinfunction "GND_12") (pintype "bidirectional"))
      (node (ref "U3") (pin "14") (pinfunction "GND_14") (pintype "bidirectional"))
      (node (ref "U3") (pin "3") (pinfunction "GND_3") (pintype "bidirectional"))
      (node (ref "U3") (pin "32") (pinfunction "GND_32") (pintype "bidirectional"))
      (node (ref "U3") (pin "37") (pinfunction "GND_37") (pintype "bidirectional"))
      (node (ref "U3") (pin "41") (pinfunction "GND_41") (pintype "bidirectional"))
      (node (ref "U3") (pin "48") (pinfunction "GND_48") (pintype "bidirectional"))
      (node (ref "U3") (pin "55") (pinfunction "GND_55") (pintype "bidirectional"))
      (node (ref "U3") (pin "56") (pinfunction "GND_56") (pintype "bidirectional"))
      (node (ref "U3") (pin "57") (pinfunction "GND_57") (pintype "bidirectional"))
      (node (ref "U3") (pin "58") (pinfunction "GND_58") (pintype "bidirectional"))
      (node (ref "U3") (pin "59") (pinfunction "GND_59") (pintype "bidirectional"))
      (node (ref "U3") (pin "60") (pinfunction "GND_60") (pintype "bidirectional"))
      (node (ref "U3") (pin "61") (pinfunction "GND_61") (pintype "bidirectional"))
      (node (ref "U3") (pin "62") (pinfunction "GND_62") (pintype "bidirectional"))
      (node (ref "U3") (pin "63") (pinfunction "GND_63") (pintype "bidirectional"))
      (node (ref "U3") (pin "64") (pinfunction "GND_64") (pintype "bidirectional"))
      (node (ref "U3") (pin "65") (pinfunction "GND_65") (pintype "bidirectional"))
      (node (ref "U3") (pin "66") (pinfunction "GND_66") (pintype "bidirectional"))
      (node (ref "U3") (pin "67") (pinfunction "GND_67") (pintype "bidirectional"))
      (node (ref "U3") (pin "68") (pinfunction "GND_68") (pintype "bidirectional"))
      (node (ref "U3") (pin "69") (pinfunction "GND_69") (pintype "bidirectional"))
      (node (ref "U3") (pin "70") (pinfunction "GND_70") (pintype "bidirectional"))
      (node (ref "U3") (pin "71") (pinfunction "GND_71") (pintype "bidirectional"))
      (node (ref "U3") (pin "72") (pinfunction "GND_72") (pintype "bidirectional"))
      (node (ref "U3") (pin "73") (pinfunction "GND_73") (pintype "bidirectional"))
      (node (ref "U3") (pin "74") (pinfunction "GND_74") (pintype "bidirectional"))
      (node (ref "U3") (pin "75") (pinfunction "GND_75") (pintype "bidirectional"))
      (node (ref "U3") (pin "76") (pinfunction "GND_76") (pintype "bidirectional"))
      (node (ref "U3") (pin "77") (pinfunction "GND_77") (pintype "bidirectional"))
      (node (ref "U3") (pin "78") (pinfunction "GND_78") (pintype "bidirectional"))
      (node (ref "U3") (pin "79") (pinfunction "GND_79") (pintype "bidirectional"))
      (node (ref "U3") (pin "80") (pinfunction "GND_80") (pintype "bidirectional"))
      (node (ref "U3") (pin "81") (pinfunction "GND_81") (pintype "bidirectional"))
      (node (ref "U3") (pin "82") (pinfunction "GND_82") (pintype "bidirectional"))
      (node (ref "U3") (pin "83") (pinfunction "GND_83") (pintype "bidirectional"))
      (node (ref "U3") (pin "84") (pinfunction "GND_84") (pintype "bidirectional"))
      (node (ref "U3") (pin "85") (pinfunction "GND_85") (pintype "bidirectional"))
      (node (ref "U3") (pin "86") (pinfunction "GND_86") (pintype "bidirectional"))
      (node (ref "U3") (pin "87") (pinfunction "GND_87") (pintype "bidirectional"))
      (node (ref "U3") (pin "88") (pinfunction "GND_88") (pintype "bidirectional"))
      (node (ref "U3") (pin "89") (pinfunction "GND_89") (pintype "bidirectional"))
      (node (ref "U3") (pin "90") (pinfunction "GND_90") (pintype "bidirectional"))
      (node (ref "U3") (pin "91") (pinfunction "GND_91") (pintype "bidirectional"))
      (node (ref "U3") (pin "92") (pinfunction "GND_92") (pintype "bidirectional"))
      (node (ref "U3") (pin "93") (pinfunction "GND_93") (pintype "bidirectional"))
      (node (ref "U3") (pin "94") (pinfunction "GND_94") (pintype "bidirectional"))
      (node (ref "U3") (pin "95") (pinfunction "GND_95") (pintype "bidirectional"))
      (node (ref "U3") (pin "96") (pinfunction "GND_96") (pintype "bidirectional"))
      (node (ref "U3") (pin "97") (pinfunction "GND_97") (pintype "bidirectional"))
      (node (ref "U3") (pin "98") (pinfunction "GND_98") (pintype "bidirectional"))
      (node (ref "U3") (pin "99") (pinfunction "GND_99") (pintype "bidirectional"))
      (node (ref "U4") (pin "2") (pinfunction "GND_2") (pintype "input"))
      (node (ref "U6") (pin "1") (pinfunction "GND_1") (pintype "bidirectional"))
      (node (ref "U7") (pin "1") (pinfunction "CTG_1") (pintype "input"))
      (node (ref "U7") (pin "4") (pinfunction "GND_4") (pintype "bidirectional"))
      (node (ref "U7") (pin "6") (pinfunction "QSTRT_6") (pintype "bidirectional"))
      (node (ref "U7") (pin "9") (pinfunction "GND_9") (pintype "bidirectional"))
    )
    (net (code "39") (name "NMEA-RX") (class "Default")
      (node (ref "BLUETOOTH_BROADCAST") (pin "6") (pinfunction "6_6") (pintype "bidirectional"))
      (node (ref "SERIAL1_CONNECTION") (pin "6") (pinfunction "6_6") (pintype "bidirectional"))
    )
    (net (code "40") (name "NMEA-TX") (class "Default")
      (node (ref "BLUETOOTH_BROADCAST") (pin "3") (pinfunction "3_3") (pintype "bidirectional"))
      (node (ref "DUAL_OUTPUT") (pin "1") (pinfunction "1_1") (pintype "passive"))
      (node (ref "SERIAL1_CONNECTION") (pin "3") (pinfunction "3_3") (pintype "bidirectional"))
    )
    (net (code "41") (name "Net-(C1-Pad1)") (class "Default")
      (node (ref "C1") (pin "1") (pinfunction "1_1") (pintype "passive"))
      (node (ref "FB1") (pin "2") (pinfunction "2_2") (pintype "passive"))
      (node (ref "R14") (pin "1") (pinfunction "1_1") (pintype "passive"))
    )
    (net (code "42") (name "Net-(D1-PadA)") (class "Default")
      (node (ref "D1") (pin "A") (pinfunction "A_A") (pintype "passive"))
      (node (ref "R11") (pin "1") (pinfunction "1_1") (pintype "passive"))
    )
    (net (code "43") (name "Net-(D2-Pad1)") (class "Default")
      (node (ref "D2") (pin "1") (pinfunction "1_1") (pintype "bidirectional"))
      (node (ref "J3") (pin "A7") (pinfunction "D-_A7") (pintype "bidirectional"))
      (node (ref "J3") (pin "B7") (pinfunction "D-_B7") (pintype "bidirectional"))
    )
    (net (code "44") (name "Net-(D2-Pad3)") (class "Default")
      (node (ref "D2") (pin "3") (pinfunction "3_3") (pintype "bidirectional"))
      (node (ref "J3") (pin "A6") (pinfunction "D+_A6") (pintype "bidirectional"))
      (node (ref "J3") (pin "B6") (pinfunction "D+_B6") (pintype "bidirectional"))
    )
    (net (code "45") (name "Net-(D3-PadA)") (class "Default")
      (node (ref "D3") (pin "A") (pinfunction "A_A") (pintype "passive"))
      (node (ref "R12") (pin "1") (pinfunction "1_1") (pintype "passive"))
    )
    (net (code "46") (name "Net-(D4-PadA)") (class "Default")
      (node (ref "D4") (pin "A") (pinfunction "A_A") (pintype "passive"))
      (node (ref "R10") (pin "2") (pinfunction "2_2") (pintype "passive"))
    )
    (net (code "47") (name "Net-(D6-Pad1)") (class "Default")
      (node (ref "D6") (pin "1") (pinfunction "1_1") (pintype "bidirectional"))
      (node (ref "J5") (pin "A7") (pinfunction "D-_A7") (pintype "bidirectional"))
      (node (ref "J5") (pin "B7") (pinfunction "D-_B7") (pintype "bidirectional"))
    )
    (net (code "48") (name "Net-(D6-Pad3)") (class "Default")
      (node (ref "D6") (pin "3") (pinfunction "3_3") (pintype "bidirectional"))
      (node (ref "J5") (pin "A6") (pinfunction "D+_A6") (pintype "bidirectional"))
      (node (ref "J5") (pin "B6") (pinfunction "D+_B6") (pintype "bidirectional"))
    )
    (net (code "49") (name "Net-(D8-PadA)") (class "Default")
      (node (ref "D8") (pin "A") (pinfunction "A_A") (pintype "passive"))
      (node (ref "R24") (pin "2") (pinfunction "2_2") (pintype "passive"))
    )
    (net (code "50") (name "Net-(D9-PadA)") (class "Default")
      (node (ref "D9") (pin "A") (pinfunction "A_A") (pintype "passive"))
      (node (ref "J3") (pin "VBUS1") (pinfunction "VBUS_VBUS1") (pintype "bidirectional"))
      (node (ref "J3") (pin "VBUS2") (pinfunction "VBUS_VBUS2") (pintype "bidirectional"))
    )
    (net (code "51") (name "Net-(D10-PadA)") (class "Default")
      (node (ref "D10") (pin "A") (pinfunction "A_A") (pintype "passive"))
      (node (ref "R25") (pin "2") (pinfunction "2_2") (pintype "passive"))
    )
    (net (code "52") (name "Net-(D11-PadA)") (class "Default")
      (node (ref "D11") (pin "A") (pinfunction "A_A") (pintype "passive"))
      (node (ref "R26") (pin "2") (pinfunction "2_2") (pintype "passive"))
    )
    (net (code "53") (name "Net-(D12-PadA)") (class "Default")
      (node (ref "D12") (pin "A") (pinfunction "A_A") (pintype "passive"))
      (node (ref "R34") (pin "2") (pinfunction "2_2") (pintype "passive"))
    )
    (net (code "54") (name "Net-(D13-BLU-C)") (class "Default")
      (node (ref "D13") (pin "1") (pinfunction "BLU-C_1") (pintype "bidirectional"))
      (node (ref "R1") (pin "1") (pinfunction "1_1") (pintype "passive"))
    )
    (net (code "55") (name "Net-(D13-GRN-C)") (class "Default")
      (node (ref "D13") (pin "3") (pinfunction "GRN-C_3") (pintype "bidirectional"))
      (node (ref "R6") (pin "1") (pinfunction "1_1") (pintype "passive"))
    )
    (net (code "56") (name "Net-(D13-RED-C)") (class "Default")
      (node (ref "D13") (pin "2") (pinfunction "RED-C_2") (pintype "bidirectional"))
      (node (ref "R8") (pin "1") (pinfunction "1_1") (pintype "passive"))
    )
    (net (code "57") (name "Net-(E1-SIGNAL)") (class "Default")
      (node (ref "D14") (pin "1") (pinfunction "1_1") (pintype "bidirectional"))
      (node (ref "E1") (pin "SIG") (pinfunction "SIGNAL_SIG") (pintype "bidirectional"))
      (node (ref "FB1") (pin "1") (pinfunction "1_1") (pintype "passive"))
      (node (ref "U3") (pin "2") (pinfunction "RF_IN_2") (pintype "bidirectional"))
    )
    (net (code "58") (name "Net-(J3-CC1)") (class "Default")
      (node (ref "J3") (pin "A5") (pinfunction "CC1_A5") (pintype "bidirectional"))
      (node (ref "R38") (pin "2") (pinfunction "2_2") (pintype "passive"))
    )
    (net (code "59") (name "Net-(J3-CC2)") (class "Default")
      (node (ref "J3") (pin "B5") (pinfunction "CC2_B5") (pintype "bidirectional"))
      (node (ref "R37") (pin "2") (pinfunction "2_2") (pintype "passive"))
    )
    (net (code "60") (name "Net-(J5-CC1)") (class "Default")
      (node (ref "J5") (pin "A5") (pinfunction "CC1_A5") (pintype "bidirectional"))
      (node (ref "R17") (pin "2") (pinfunction "2_2") (pintype "passive"))
    )
    (net (code "61") (name "Net-(J5-CC2)") (class "Default")
      (node (ref "J5") (pin "B5") (pinfunction "CC2_B5") (pintype "bidirectional"))
      (node (ref "R16") (pin "2") (pinfunction "2_2") (pintype "passive"))
    )
    (net (code "62") (name "Net-(J5-VBUS-PadVBUS1)") (class "Default")
      (node (ref "J5") (pin "VBUS1") (pinfunction "VBUS_VBUS1") (pintype "bidirectional"))
      (node (ref "J5") (pin "VBUS2") (pinfunction "VBUS_VBUS2") (pintype "bidirectional"))
      (node (ref "MEAS") (pin "1") (pinfunction "1_1") (pintype "passive"))
      (node (ref "MEAS") (pin "3") (pinfunction "1_3") (pintype "passive"))
    )
    (net (code "63") (name "Net-(J8-+)") (class "Default")
      (node (ref "J8") (pin "2") (pinfunction "+_2") (pintype "bidirectional"))
      (node (ref "MEAS1") (pin "1") (pinfunction "1_1") (pintype "passive"))
      (node (ref "MEAS1") (pin "3") (pinfunction "1_3") (pintype "passive"))
    )
    (net (code "64") (name "Net-(Q2A-B)") (class "Default")
      (node (ref "Q2") (pin "5") (pinfunction "B_5") (pintype "passive"))
      (node (ref "R23") (pin "2") (pinfunction "2_2") (pintype "passive"))
    )
    (net (code "65") (name "Net-(Q2A-E)") (class "Default")
      (node (ref "Q2") (pin "4") (pinfunction "E_4") (pintype "passive"))
      (node (ref "R29") (pin "1") (pinfunction "1_1") (pintype "passive"))
      (node (ref "U6") (pin "14") (pinfunction "~{RTS}_14") (pintype "bidirectional"))
    )
    (net (code "66") (name "Net-(Q2B-B)") (class "Default")
      (node (ref "Q2") (pin "2") (pinfunction "B_2") (pintype "passive"))
      (node (ref "R29") (pin "2") (pinfunction "2_2") (pintype "passive"))
    )
    (net (code "67") (name "Net-(Q2B-E)") (class "Default")
      (node (ref "Q2") (pin "1") (pinfunction "E_1") (pintype "passive"))
      (node (ref "R23") (pin "1") (pinfunction "1_1") (pintype "passive"))
      (node (ref "U6") (pin "13") (pinfunction "~{DTR}_13") (pintype "bidirectional"))
    )
    (net (code "68") (name "Net-(R2A-1)") (class "Default")
      (node (ref "R2") (pin "P1") (pinfunction "1_P1") (pintype "passive"))
      (node (ref "U3") (pin "53") (pinfunction "TIMEPULSE_53") (pintype "bidirectional"))
    )
    (net (code "69") (name "Net-(R2B-1)") (class "Default")
      (node (ref "R2") (pin "P2") (pinfunction "1_P2") (pintype "passive"))
      (node (ref "U3") (pin "47") (pinfunction "D_SEL_47") (pintype "bidirectional"))
    )
    (net (code "70") (name "Net-(R2C-1)") (class "Default")
      (node (ref "R2") (pin "P3") (pinfunction "1_P3") (pintype "passive"))
      (node (ref "U3") (pin "50") (pinfunction "~{SAFEBOOT}_50") (pintype "bidirectional"))
    )
    (net (code "71") (name "Net-(R2D-1)") (class "Default")
      (node (ref "R2") (pin "P4") (pinfunction "1_P4") (pintype "passive"))
      (node (ref "U3") (pin "49") (pinfunction "~{RESET}_49") (pintype "bidirectional"))
    )
    (net (code "72") (name "Net-(R4A-2)") (class "Default")
      (node (ref "R4") (pin "P8") (pinfunction "2_P8") (pintype "passive"))
      (node (ref "U3") (pin "19") (pinfunction "GEO_STAT_19") (pintype "bidirectional"))
    )
    (net (code "73") (name "Net-(R4B-2)") (class "Default")
      (node (ref "R4") (pin "P7") (pinfunction "2_P7") (pintype "passive"))
      (node (ref "U3") (pin "20") (pinfunction "RTK_STAT_20") (pintype "bidirectional"))
    )
    (net (code "74") (name "Net-(R4C-2)") (class "Default")
      (node (ref "R4") (pin "P6") (pinfunction "2_P6") (pintype "passive"))
      (node (ref "U3") (pin "26") (pinfunction "RX2_26") (pintype "bidirectional"))
    )
    (net (code "75") (name "Net-(R4D-2)") (class "Default")
      (node (ref "R4") (pin "P5") (pinfunction "2_P5") (pintype "passive"))
      (node (ref "U3") (pin "27") (pinfunction "TX2_27") (pintype "bidirectional"))
    )
    (net (code "76") (name "Net-(R9A-1)") (class "Default")
      (node (ref "R9") (pin "P1") (pinfunction "1_P1") (pintype "passive"))
      (node (ref "U3") (pin "46") (pinfunction "TX_READY_46") (pintype "bidirectional"))
    )
    (net (code "77") (name "Net-(R9B-1)") (class "Default")
      (node (ref "R9") (pin "P2") (pinfunction "1_P2") (pintype "passive"))
      (node (ref "U3") (pin "45") (pinfunction "SCL/CLK_45") (pintype "bidirectional"))
    )
    (net (code "78") (name "Net-(R9C-1)") (class "Default")
      (node (ref "R9") (pin "P3") (pinfunction "1_P3") (pintype "passive"))
      (node (ref "U3") (pin "44") (pinfunction "SDA/~{CS}_44") (pintype "bidirectional"))
    )
    (net (code "79") (name "Net-(R9D-1)") (class "Default")
      (node (ref "R9") (pin "P4") (pinfunction "1_P4") (pintype "passive"))
      (node (ref "U3") (pin "43") (pinfunction "RX/MOSI_43") (pintype "bidirectional"))
    )
    (net (code "80") (name "Net-(R18-Pad2)") (class "Default")
      (node (ref "R18") (pin "2") (pinfunction "2_2") (pintype "bidirectional"))
      (node (ref "R30") (pin "2") (pinfunction "2_2") (pintype "passive"))
      (node (ref "R5") (pin "2") (pinfunction "2_2") (pintype "passive"))
    )
    (net (code "81") (name "Net-(U3-TX{slash}MISO)") (class "Default")
      (node (ref "R3") (pin "1") (pinfunction "1_1") (pintype "passive"))
      (node (ref "U3") (pin "42") (pinfunction "TX/MISO_42") (pintype "bidirectional"))
    )
    (net (code "82") (name "Net-(U3-USB_D+)") (class "Default")
      (node (ref "R27") (pin "2") (pinfunction "2_2") (pintype "passive"))
      (node (ref "U3") (pin "40") (pinfunction "USB_D+_40") (pintype "bidirectional"))
    )
    (net (code "83") (name "Net-(U3-USB_D-)") (class "Default")
      (node (ref "R28") (pin "2") (pinfunction "2_2") (pintype "passive"))
      (node (ref "U3") (pin "39") (pinfunction "USB_D-_39") (pintype "bidirectional"))
    )
    (net (code "84") (name "Net-(U3-V_RF)") (class "Default")
      (node (ref "R14") (pin "2") (pinfunction "2_2") (pintype "passive"))
      (node (ref "U3") (pin "7") (pinfunction "V_RF_7") (pintype "bidirectional"))
    )
    (net (code "85") (name "Net-(U6-UD+)") (class "Default")
      (node (ref "D2") (pin "4") (pinfunction "4_4") (pintype "bidirectional"))
      (node (ref "U6") (pin "5") (pinfunction "UD+_5") (pintype "bidirectional"))
    )
    (net (code "86") (name "Net-(U6-UD-)") (class "Default")
      (node (ref "D2") (pin "6") (pinfunction "6_6") (pintype "bidirectional"))
      (node (ref "U6") (pin "6") (pinfunction "UD-_6") (pintype "bidirectional"))
    )
    (net (code "87") (name "Net-(U10-PROG)") (class "Default")
      (node (ref "R7") (pin "2") (pinfunction "2_2") (pintype "passive"))
      (node (ref "U10") (pin "6") (pinfunction "PROG_6") (pintype "bidirectional"))
    )
    (net (code "88") (name "Net-(U10-THERM)") (class "Default")
      (node (ref "R5") (pin "1") (pinfunction "1_1") (pintype "passive"))
      (node (ref "U10") (pin "8") (pinfunction "THERM_8") (pintype "bidirectional"))
    )
    (net (code "89") (name "VIN") (class "Default")
      (node (ref "C9") (pin "1") (pinfunction "1_1") (pintype "passive"))
      (node (ref "D13") (pin "6") (pinfunction "BLU-A_6") (pintype "bidirectional"))
      (node (ref "D2") (pin "5") (pinfunction "5_5") (pintype "power_in"))
      (node (ref "D6") (pin "5") (pinfunction "5_5") (pintype "power_in"))
      (node (ref "D7") (pin "C") (pinfunction "C_C") (pintype "passive"))
      (node (ref "D9") (pin "C") (pinfunction "C_C") (pintype "passive"))
      (node (ref "J7") (pin "2") (pinfunction "1_2") (pintype "passive"))
      (node (ref "MEAS") (pin "2") (pinfunction "2_2") (pintype "passive"))
      (node (ref "MEAS") (pin "4") (pinfunction "2_4") (pintype "passive"))
      (node (ref "U10") (pin "1") (pinfunction "VDD_1") (pintype "bidirectional"))
      (node (ref "U10") (pin "2") (pinfunction "VDD_2") (pintype "bidirectional"))
    )
    (net (code "90") (name "V_BATT") (class "Default")
      (node (ref "C15") (pin "1") (pinfunction "1_1") (pintype "passive"))
      (node (ref "C17") (pin "1") (pinfunction "1_1") (pintype "passive"))
      (node (ref "C8") (pin "1") (pinfunction "1_1") (pintype "passive"))
      (node (ref "D7") (pin "A") (pinfunction "A_A") (pintype "passive"))
      (node (ref "J10") (pin "1") (pinfunction "1_1") (pintype "passive"))
      (node (ref "MEAS1") (pin "2") (pinfunction "2_2") (pintype "passive"))
      (node (ref "MEAS1") (pin "4") (pinfunction "2_4") (pintype "passive"))
      (node (ref "U10") (pin "10") (pinfunction "VBAT_10") (pintype "bidirectional"))
      (node (ref "U10") (pin "9") (pinfunction "VBAT_9") (pintype "bidirectional"))
      (node (ref "U4") (pin "1") (pinfunction "IN_1") (pintype "input"))
      (node (ref "U4") (pin "3") (pinfunction "EN_3") (pintype "input"))
      (node (ref "U7") (pin "2") (pinfunction "CELL_2") (pintype "input"))
      (node (ref "U7") (pin "3") (pinfunction "VDD_3") (pintype "bidirectional"))
    )
    (net (code "91") (name "ZED-RXI1") (class "Default")
      (node (ref "J15") (pin "2") (pinfunction "2_2") (pintype "passive"))
      (node (ref "R9") (pin "P5") (pinfunction "2_P5") (pintype "passive"))
      (node (ref "SERIAL1_CONNECTION") (pin "5") (pinfunction "5_5") (pintype "bidirectional"))
    )
    (net (code "92") (name "ZED-RXI2") (class "Default")
      (node (ref "BLUETOOTH_BROADCAST") (pin "4") (pinfunction "4_4") (pintype "bidirectional"))
      (node (ref "J11") (pin "2") (pinfunction "2_2") (pintype "passive"))
      (node (ref "J9") (pin "3") (pinfunction "3_3") (pintype "passive"))
      (node (ref "R4") (pin "P3") (pinfunction "1_P3") (pintype "passive"))
    )
    (net (code "93") (name "ZED-TXO1") (class "Default")
      (node (ref "J15") (pin "1") (pinfunction "1_1") (pintype "passive"))
      (node (ref "R3") (pin "2") (pinfunction "2_2") (pintype "passive"))
      (node (ref "SERIAL1_CONNECTION") (pin "2") (pinfunction "2_2") (pintype "bidirectional"))
    )
    (net (code "94") (name "ZED-TXO2") (class "Default")
      (node (ref "BLUETOOTH_BROADCAST") (pin "1") (pinfunction "1_1") (pintype "bidirectional"))
      (node (ref "J11") (pin "3") (pinfunction "3_3") (pintype "passive"))
      (node (ref "J9") (pin "2") (pinfunction "2_2") (pintype "passive"))
      (node (ref "R4") (pin "P4") (pinfunction "1_P4") (pintype "passive"))
    )
    (net (code "95") (name "ZED_D_SEL") (class "Default")
      (node (ref "J18") (pin "5") (pinfunction "5_5") (pintype "passive"))
      (node (ref "R2") (pin "P7") (pinfunction "2_P7") (pintype "passive"))
    )
    (net (code "96") (name "ZED_FENCE_STAT") (class "Default")
      (node (ref "J1") (pin "2") (pinfunction "2_2") (pintype "passive"))
      (node (ref "R4") (pin "P1") (pinfunction "1_P1") (pintype "passive"))
    )
    (net (code "97") (name "ZED_PPS_STAT") (class "Default")
      (node (ref "J18") (pin "4") (pinfunction "4_4") (pintype "passive"))
      (node (ref "R11") (pin "2") (pinfunction "2_2") (pintype "passive"))
      (node (ref "R2") (pin "P8") (pinfunction "2_P8") (pintype "passive"))
      (node (ref "ZED_CONTROL") (pin "1") (pinfunction "1_1") (pintype "bidirectional"))
    )
    (net (code "98") (name "ZED_RTK_STAT") (class "Default")
      (node (ref "D3") (pin "C") (pinfunction "C_C") (pintype "passive"))
      (node (ref "J1") (pin "3") (pinfunction "3_3") (pintype "passive"))
      (node (ref "R4") (pin "P2") (pinfunction "1_P2") (pintype "passive"))
    )
    (net (code "99") (name "ZED_~{SAFE}") (class "Default")
      (node (ref "J18") (pin "3") (pinfunction "3_3") (pintype "passive"))
      (node (ref "R2") (pin "P6") (pinfunction "2_P6") (pintype "passive"))
    )
    (net (code "100") (name "unconnected-(J8-PAD1-PadNC1)") (class "Default")
      (node (ref "J8") (pin "NC1") (pinfunction "PAD1_NC1") (pintype "bidirectional"))
    )
    (net (code "101") (name "unconnected-(J8-PAD2-PadNC2)") (class "Default")
      (node (ref "J8") (pin "NC2") (pinfunction "PAD2_NC2") (pintype "bidirectional"))
    )
    (net (code "102") (name "unconnected-(J16-DAT1{slash}NC-PadDAT1)") (class "Default")
      (node (ref "J16") (pin "DAT1") (pinfunction "DAT1/NC_DAT1") (pintype "bidirectional"))
    )
    (net (code "103") (name "unconnected-(J16-DAT2{slash}NC-PadDAT2)") (class "Default")
      (node (ref "J16") (pin "DAT2") (pinfunction "DAT2/NC_DAT2") (pintype "bidirectional"))
    )
    (net (code "104") (name "unconnected-(U2-NC-Pad4)") (class "Default")
      (node (ref "U2") (pin "4") (pinfunction "NC_4") (pintype "no_connect"))
    )
    (net (code "105") (name "unconnected-(U3-ANT_DETECT-Pad4)") (class "Default")
      (node (ref "U3") (pin "4") (pinfunction "ANT_DETECT_4") (pintype "bidirectional"))
    )
    (net (code "106") (name "unconnected-(U3-ANT_OFF-Pad5)") (class "Default")
      (node (ref "U3") (pin "5") (pinfunction "ANT_OFF_5") (pintype "bidirectional"))
    )
    (net (code "107") (name "unconnected-(U3-EXTINT-Pad51)") (class "Default")
      (node (ref "U3") (pin "51") (pinfunction "EXTINT_51") (pintype "bidirectional"))
    )
    (net (code "108") (name "unconnected-(U3-~{ANT_SHORT}-Pad6)") (class "Default")
      (node (ref "U3") (pin "6") (pinfunction "~{ANT_SHORT}_6") (pintype "bidirectional"))
    )
    (net (code "109") (name "unconnected-(U4-NC-Pad4)") (class "Default")
      (node (ref "U4") (pin "4") (pinfunction "NC_4") (pintype "no_connect"))
    )
    (net (code "110") (name "unconnected-(U6-R232-Pad15)") (class "Default")
      (node (ref "U6") (pin "15") (pinfunction "R232_15") (pintype "bidirectional"))
    )
    (net (code "111") (name "unconnected-(U6-~{CTS}-Pad9)") (class "Default")
      (node (ref "U6") (pin "9") (pinfunction "~{CTS}_9") (pintype "bidirectional"))
    )
    (net (code "112") (name "unconnected-(U6-~{DCD}-Pad12)") (class "Default")
      (node (ref "U6") (pin "12") (pinfunction "~{DCD}_12") (pintype "bidirectional"))
    )
    (net (code "113") (name "unconnected-(U6-~{DSR}-Pad10)") (class "Default")
      (node (ref "U6") (pin "10") (pinfunction "~{DSR}_10") (pintype "bidirectional"))
    )
    (net (code "114") (name "unconnected-(U6-~{RI}-Pad11)") (class "Default")
      (node (ref "U6") (pin "11") (pinfunction "~{RI}_11") (pintype "bidirectional"))
    )
    (net (code "115") (name "unconnected-(U10-STAT2-Pad4)") (class "Default")
      (node (ref "U10") (pin "4") (pinfunction "STAT2_4") (pintype "bidirectional"))
    )
    (net (code "116") (name "unconnected-(U10-~{PG}-Pad7)") (class "Default")
      (node (ref "U10") (pin "7") (pinfunction "~{PG}_7") (pintype "bidirectional"))
    )
  )
)
